# misc.net
KiCad netlist of a schematic drawn in Altium Designer
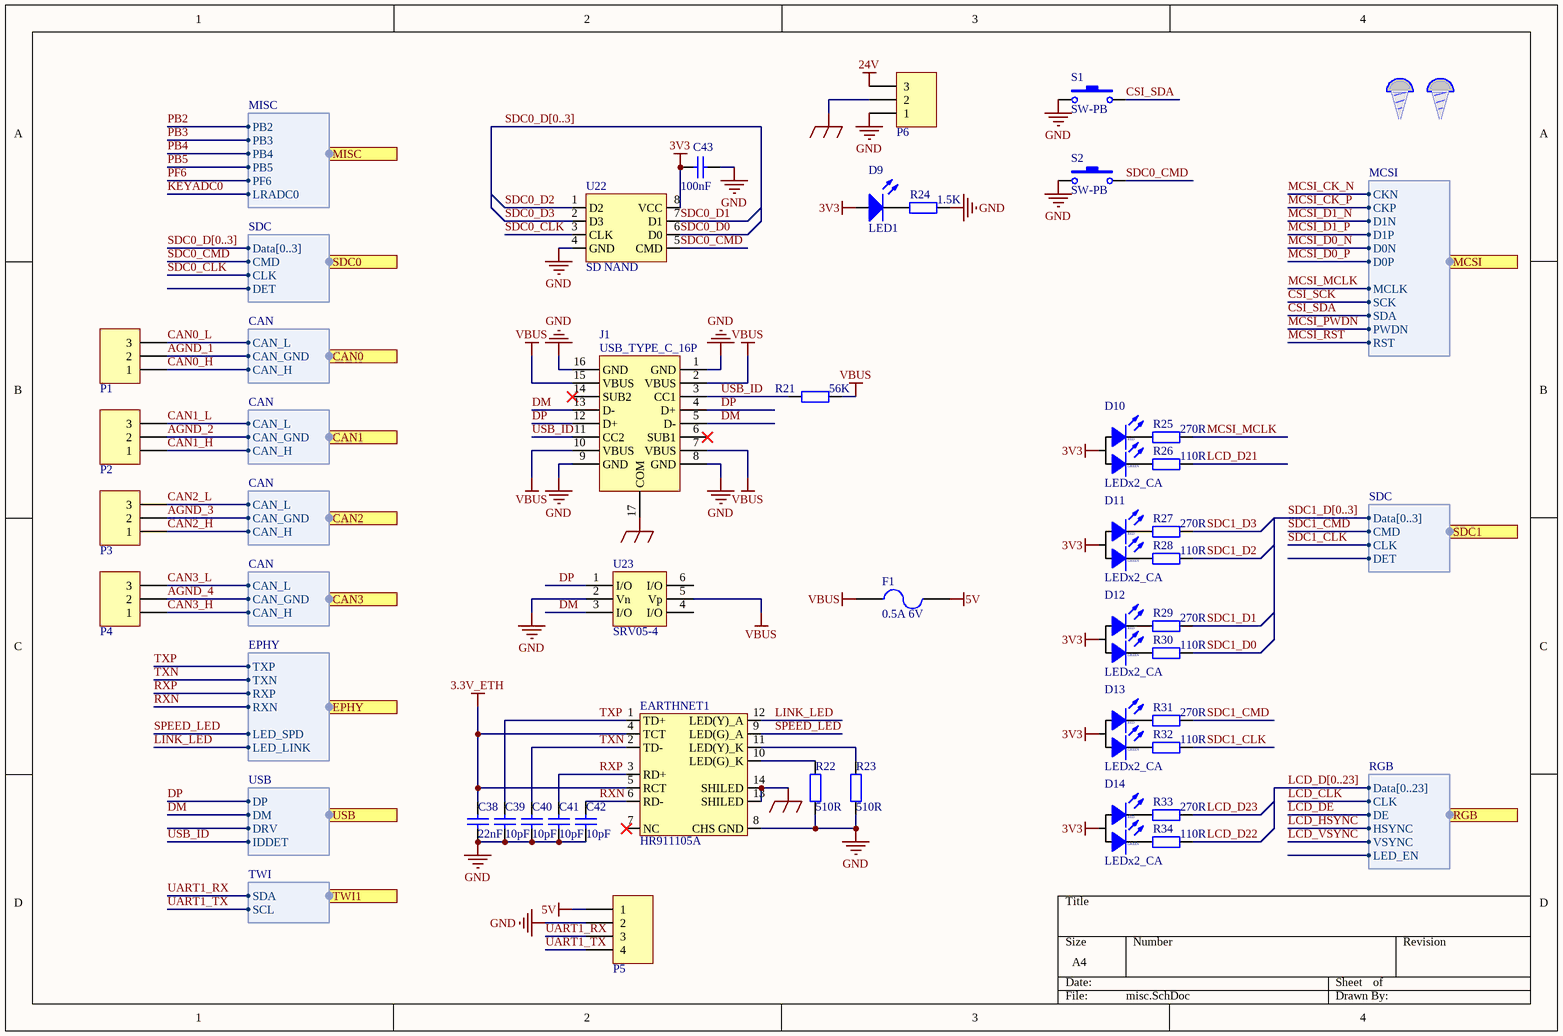
[diagram p0: misc.SchDoc]

(export (version "E")
  (design (tool "Eeschema 10.0.6"))
  (components
    (comp (ref "C38")
      (value "22nF")
      (footprint "CAPC1608L")
      (description "Capacitor")
      (fields (field (name "PUBLISHER") "Altium Limited"))
      (libsource (lib "Peace的集成库") (part "Cap1"))
    )
    (comp (ref "C39")
      (value "10pF")
      (footprint "CAPC1608L")
      (description "Capacitor")
      (fields (field (name "PUBLISHER") "Altium Limited"))
      (libsource (lib "Peace的集成库") (part "Cap1"))
    )
    (comp (ref "C40")
      (value "10pF")
      (footprint "CAPC1608L")
      (description "Capacitor")
      (fields (field (name "PUBLISHER") "Altium Limited"))
      (libsource (lib "Peace的集成库") (part "Cap1"))
    )
    (comp (ref "C41")
      (value "10pF")
      (footprint "CAPC1608L")
      (description "Capacitor")
      (fields (field (name "PUBLISHER") "Altium Limited"))
      (libsource (lib "Peace的集成库") (part "Cap1"))
    )
    (comp (ref "C42")
      (value "10pF")
      (footprint "CAPC1608L")
      (description "Capacitor")
      (fields (field (name "PUBLISHER") "Altium Limited"))
      (libsource (lib "Peace的集成库") (part "Cap1"))
    )
    (comp (ref "C43")
      (value "100nF")
      (footprint "CAPC1608L")
      (description "Capacitor")
      (fields (field (name "PUBLISHER") "Altium Limited"))
      (libsource (lib "Peace的集成库") (part "Cap1"))
    )
    (comp (ref "D9")
      (value "LED1")
      (footprint "LED_3")
      (description "Typical RED GaAs LED")
      (fields (field (name "PUBLISHER") "Altium Limited"))
      (libsource (lib "Peace的集成库") (part "LED1"))
    )
    (comp (ref "D10")
      (value "LEDx2_CA")
      (footprint "LED_3x2")
      (description "共阳红绿双色二极管")
      (fields (field (name "PUBLISHER") "Altium Limited"))
      (libsource (lib "Peace的集成库") (part "LEDx2_CA"))
    )
    (comp (ref "D11")
      (value "LEDx2_CA")
      (footprint "LED_3x2")
      (description "共阳红绿双色二极管")
      (fields (field (name "PUBLISHER") "Altium Limited"))
      (libsource (lib "Peace的集成库") (part "LEDx2_CA"))
    )
    (comp (ref "D12")
      (value "LEDx2_CA")
      (footprint "LED_3x2")
      (description "共阳红绿双色二极管")
      (fields (field (name "PUBLISHER") "Altium Limited"))
      (libsource (lib "Peace的集成库") (part "LEDx2_CA"))
    )
    (comp (ref "D13")
      (value "LEDx2_CA")
      (footprint "LED_3x2")
      (description "共阳红绿双色二极管")
      (fields (field (name "PUBLISHER") "Altium Limited"))
      (libsource (lib "Peace的集成库") (part "LEDx2_CA"))
    )
    (comp (ref "D14")
      (value "LEDx2_CA")
      (footprint "LED_3x2")
      (description "共阳红绿双色二极管")
      (fields (field (name "PUBLISHER") "Altium Limited"))
      (libsource (lib "Peace的集成库") (part "LEDx2_CA"))
    )
    (comp (ref "EARTHNET1")
      (value "HR911105A")
      (footprint "HR911105A")
      (libsource (lib "原理图库") (part "HR911105A"))
    )
    (comp (ref "F1")
      (value "0.5A 6V")
      (footprint "FUSE2012L")
      (description "Fuse")
      (fields (field (name "PUBLISHER") "Altium Limited"))
      (libsource (lib "Peace的集成库") (part "Fuse 2"))
    )
    (comp (ref "J1")
      (value "USB_TYPE_C_16P")
      (footprint "USB_TYPEC_16P")
      (libsource (lib "Peace的集成库") (part "USB_TYPE_C_16P"))
    )
    (comp (ref "M1") (value "M") (footprint "M3") (libsource (lib "Peace的集成库") (part "M")))
    (comp (ref "M2") (value "M") (footprint "M3") (libsource (lib "Peace的集成库") (part "M")))
    (comp (ref "P1")
      (value "Header 3")
      (footprint "KF2EDGR-5.08-3P_S")
      (description "Header, 3-Pin")
      (fields (field (name "PUBLISHER") "Altium Limited"))
      (libsource (lib "Peace的集成库") (part "Header 3"))
    )
    (comp (ref "P2")
      (value "Header 3")
      (footprint "KF2EDGR-5.08-3P_S")
      (description "Header, 3-Pin")
      (fields (field (name "PUBLISHER") "Altium Limited"))
      (libsource (lib "Peace的集成库") (part "Header 3"))
    )
    (comp (ref "P3")
      (value "Header 3")
      (footprint "KF2EDGR-5.08-3P_S")
      (description "Header, 3-Pin")
      (fields (field (name "PUBLISHER") "Altium Limited"))
      (libsource (lib "Peace的集成库") (part "Header 3"))
    )
    (comp (ref "P4")
      (value "Header 3")
      (footprint "KF2EDGR-5.08-3P_S")
      (description "Header, 3-Pin")
      (fields (field (name "PUBLISHER") "Altium Limited"))
      (libsource (lib "Peace的集成库") (part "Header 3"))
    )
    (comp (ref "P5")
      (value "Header 4")
      (footprint "HDR1X4")
      (description "Header, 4-Pin")
      (fields (field (name "PUBLISHER") "Altium Limited"))
      (libsource (lib "Peace的集成库") (part "Header 4"))
    )
    (comp (ref "P6")
      (value "Header 3")
      (footprint "KF2EDGR-5.08-3P_S")
      (description "Header, 3-Pin")
      (fields (field (name "PUBLISHER") "Altium Limited"))
      (libsource (lib "") (part "Header 3_1"))
    )
    (comp (ref "R21")
      (value "56K")
      (footprint "RESC1005L")
      (description "Resistor")
      (fields (field (name "PUBLISHER") "Altium Limited"))
      (libsource (lib "") (part "Res1_1"))
    )
    (comp (ref "R22")
      (value "510R")
      (footprint "RESC1608L")
      (description "Resistor")
      (fields (field (name "PUBLISHER") "Altium Limited"))
      (libsource (lib "Peace的集成库") (part "Res1"))
    )
    (comp (ref "R23")
      (value "510R")
      (footprint "RESC1608L")
      (description "Resistor")
      (fields (field (name "PUBLISHER") "Altium Limited"))
      (libsource (lib "Peace的集成库") (part "Res1"))
    )
    (comp (ref "R24")
      (value "1.5K")
      (footprint "RESC1608L")
      (description "Resistor")
      (fields (field (name "PUBLISHER") "Altium Limited"))
      (libsource (lib "") (part "Res1_1"))
    )
    (comp (ref "R25")
      (value "270R")
      (footprint "RESC1608L")
      (description "Resistor")
      (fields (field (name "PUBLISHER") "Altium Limited"))
      (libsource (lib "") (part "Res1_1"))
    )
    (comp (ref "R26")
      (value "110R")
      (footprint "RESC1608L")
      (description "Resistor")
      (fields (field (name "PUBLISHER") "Altium Limited"))
      (libsource (lib "") (part "Res1_1"))
    )
    (comp (ref "R27")
      (value "270R")
      (footprint "RESC1608L")
      (description "Resistor")
      (fields (field (name "PUBLISHER") "Altium Limited"))
      (libsource (lib "") (part "Res1_1"))
    )
    (comp (ref "R28")
      (value "110R")
      (footprint "RESC1608L")
      (description "Resistor")
      (fields (field (name "PUBLISHER") "Altium Limited"))
      (libsource (lib "") (part "Res1_1"))
    )
    (comp (ref "R29")
      (value "270R")
      (footprint "RESC1608L")
      (description "Resistor")
      (fields (field (name "PUBLISHER") "Altium Limited"))
      (libsource (lib "") (part "Res1_1"))
    )
    (comp (ref "R30")
      (value "110R")
      (footprint "RESC1608L")
      (description "Resistor")
      (fields (field (name "PUBLISHER") "Altium Limited"))
      (libsource (lib "") (part "Res1_1"))
    )
    (comp (ref "R31")
      (value "270R")
      (footprint "RESC1608L")
      (description "Resistor")
      (fields (field (name "PUBLISHER") "Altium Limited"))
      (libsource (lib "") (part "Res1_1"))
    )
    (comp (ref "R32")
      (value "110R")
      (footprint "RESC1608L")
      (description "Resistor")
      (fields (field (name "PUBLISHER") "Altium Limited"))
      (libsource (lib "") (part "Res1_1"))
    )
    (comp (ref "R33")
      (value "270R")
      (footprint "RESC1608L")
      (description "Resistor")
      (fields (field (name "PUBLISHER") "Altium Limited"))
      (libsource (lib "") (part "Res1_1"))
    )
    (comp (ref "R34")
      (value "110R")
      (footprint "RESC1608L")
      (description "Resistor")
      (fields (field (name "PUBLISHER") "Altium Limited"))
      (libsource (lib "") (part "Res1_1"))
    )
    (comp (ref "S1")
      (value "SW-PB")
      (footprint "SW_4.5x3.8")
      (description "Switch")
      (fields (field (name "PUBLISHER") "Altium Limited"))
      (libsource (lib "Peace的集成库") (part "SW-PB"))
    )
    (comp (ref "S2")
      (value "SW-PB")
      (footprint "SW-3x6")
      (description "Switch")
      (fields (field (name "PUBLISHER") "Altium Limited"))
      (libsource (lib "Peace的集成库") (part "SW-PB"))
    )
    (comp (ref "U22")
      (value "SD NAND")
      (footprint "QFN8_L")
      (description "贴片式SD卡")
      (libsource (lib "Peace的集成库") (part "SD NAND"))
    )
    (comp (ref "U23")
      (value "SRV05-4")
      (footprint "SOT23-6_L")
      (libsource (lib "Peace的集成库") (part "NUP4201"))
    )
  )
  (nets
    (net (code "10") (name "/AGND_1") (class "Default")
      (node (ref "P1") (pin "2") (pinfunction "2_2") (pintype "passive"))
    )
    (net (code "11") (name "/AGND_2") (class "Default")
      (node (ref "P2") (pin "2") (pinfunction "2_2") (pintype "passive"))
    )
    (net (code "12") (name "/AGND_3") (class "Default")
      (node (ref "P3") (pin "2") (pinfunction "2_2") (pintype "passive"))
    )
    (net (code "13") (name "/AGND_4") (class "Default")
      (node (ref "P4") (pin "2") (pinfunction "2_2") (pintype "passive"))
    )
    (net (code "14") (name "/CAN0_H") (class "Default")
      (node (ref "P1") (pin "1") (pinfunction "1_1") (pintype "passive"))
    )
    (net (code "15") (name "/CAN0_L") (class "Default")
      (node (ref "P1") (pin "3") (pinfunction "3_3") (pintype "passive"))
    )
    (net (code "16") (name "/CAN1_H") (class "Default")
      (node (ref "P2") (pin "1") (pinfunction "1_1") (pintype "passive"))
    )
    (net (code "17") (name "/CAN1_L") (class "Default")
      (node (ref "P2") (pin "3") (pinfunction "3_3") (pintype "passive"))
    )
    (net (code "18") (name "/CAN2_H") (class "Default")
      (node (ref "P3") (pin "1") (pinfunction "1_1") (pintype "passive"))
    )
    (net (code "19") (name "/CAN2_L") (class "Default")
      (node (ref "P3") (pin "3") (pinfunction "3_3") (pintype "passive"))
    )
    (net (code "20") (name "/CAN3_H") (class "Default")
      (node (ref "P4") (pin "1") (pinfunction "1_1") (pintype "passive"))
    )
    (net (code "21") (name "/CAN3_L") (class "Default")
      (node (ref "P4") (pin "3") (pinfunction "3_3") (pintype "passive"))
    )
    (net (code "23") (name "/CSI_SDA") (class "Default")
      (node (ref "S1") (pin "2") (pinfunction "2_2") (pintype "passive"))
    )
    (net (code "24") (name "/DM") (class "Default")
      (node (ref "J1") (pin "13") (pinfunction "D-_13") (pintype "passive"))
      (node (ref "J1") (pin "5") (pinfunction "D-_5") (pintype "passive"))
      (node (ref "U23") (pin "3") (pinfunction "I/O_3") (pintype "passive"))
    )
    (net (code "25") (name "/DP") (class "Default")
      (node (ref "J1") (pin "12") (pinfunction "D+_12") (pintype "passive"))
      (node (ref "J1") (pin "4") (pinfunction "D+_4") (pintype "passive"))
      (node (ref "U23") (pin "1") (pinfunction "I/O_1") (pintype "passive"))
    )
    (net (code "28") (name "/LCD_D21") (class "Default")
      (node (ref "R26") (pin "2") (pinfunction "2_2") (pintype "passive"))
    )
    (net (code "29") (name "/LCD_D22") (class "Default")
      (node (ref "R34") (pin "2") (pinfunction "2_2") (pintype "passive"))
    )
    (net (code "30") (name "/LCD_D23") (class "Default")
      (node (ref "R33") (pin "2") (pinfunction "2_2") (pintype "passive"))
    )
    (net (code "34") (name "/LINK_LED") (class "Default")
      (node (ref "EARTHNET1") (pin "12") (pinfunction "LED(Y)_A_12") (pintype "passive"))
    )
    (net (code "41") (name "/MCSI_MCLK") (class "Default")
      (node (ref "R25") (pin "2") (pinfunction "2_2") (pintype "passive"))
    )
    (net (code "50") (name "/RXN") (class "Default")
      (node (ref "C42") (pin "2") (pinfunction "2_2") (pintype "passive"))
      (node (ref "EARTHNET1") (pin "6") (pinfunction "RD-_6") (pintype "passive"))
    )
    (net (code "51") (name "/RXP") (class "Default")
      (node (ref "C41") (pin "2") (pinfunction "2_2") (pintype "passive"))
      (node (ref "EARTHNET1") (pin "3") (pinfunction "RD+_3") (pintype "passive"))
    )
    (net (code "52") (name "/SDC0_CLK") (class "Default")
      (node (ref "U22") (pin "3") (pinfunction "CLK_3") (pintype "passive"))
    )
    (net (code "53") (name "/SDC0_CMD") (class "Default")
      (node (ref "S2") (pin "2") (pinfunction "2_2") (pintype "passive"))
      (node (ref "U22") (pin "5") (pinfunction "CMD_5") (pintype "passive"))
    )
    (net (code "54") (name "/SDC0_D0") (class "Default")
      (node (ref "U22") (pin "6") (pinfunction "D0_6") (pintype "passive"))
    )
    (net (code "55") (name "/SDC0_D1") (class "Default")
      (node (ref "U22") (pin "7") (pinfunction "D1_7") (pintype "passive"))
    )
    (net (code "56") (name "/SDC0_D2") (class "Default")
      (node (ref "U22") (pin "1") (pinfunction "D2_1") (pintype "passive"))
    )
    (net (code "57") (name "/SDC0_D3") (class "Default")
      (node (ref "U22") (pin "2") (pinfunction "D3_2") (pintype "passive"))
    )
    (net (code "60") (name "/SDC1_CLK") (class "Default")
      (node (ref "R32") (pin "2") (pinfunction "2_2") (pintype "passive"))
    )
    (net (code "61") (name "/SDC1_CMD") (class "Default")
      (node (ref "R31") (pin "2") (pinfunction "2_2") (pintype "passive"))
    )
    (net (code "62") (name "/SDC1_D0") (class "Default")
      (node (ref "R30") (pin "2") (pinfunction "2_2") (pintype "passive"))
    )
    (net (code "63") (name "/SDC1_D1") (class "Default")
      (node (ref "R29") (pin "2") (pinfunction "2_2") (pintype "passive"))
    )
    (net (code "64") (name "/SDC1_D2") (class "Default")
      (node (ref "R28") (pin "2") (pinfunction "2_2") (pintype "passive"))
    )
    (net (code "65") (name "/SDC1_D3") (class "Default")
      (node (ref "R27") (pin "2") (pinfunction "2_2") (pintype "passive"))
    )
    (net (code "67") (name "/SPEED_LED") (class "Default")
      (node (ref "EARTHNET1") (pin "9") (pinfunction "LED(G)_A_9") (pintype "passive"))
    )
    (net (code "68") (name "/TXN") (class "Default")
      (node (ref "C40") (pin "2") (pinfunction "2_2") (pintype "passive"))
      (node (ref "EARTHNET1") (pin "2") (pinfunction "TD-_2") (pintype "passive"))
    )
    (net (code "69") (name "/TXP") (class "Default")
      (node (ref "C39") (pin "2") (pinfunction "2_2") (pintype "passive"))
      (node (ref "EARTHNET1") (pin "1") (pinfunction "TD+_1") (pintype "passive"))
    )
    (net (code "70") (name "/UART1_RX") (class "Default")
      (node (ref "P5") (pin "3") (pinfunction "3_3") (pintype "passive"))
    )
    (net (code "71") (name "/UART1_TX") (class "Default")
      (node (ref "P5") (pin "4") (pinfunction "4_4") (pintype "passive"))
    )
    (net (code "72") (name "/USB_ID") (class "Default")
      (node (ref "J1") (pin "11") (pinfunction "CC2_11") (pintype "passive"))
      (node (ref "J1") (pin "3") (pinfunction "CC1_3") (pintype "passive"))
      (node (ref "R21") (pin "1") (pinfunction "1_1") (pintype "passive"))
    )
    (net (code "82") (name "3.3V_ETH") (class "Default")
      (node (ref "C38") (pin "2") (pinfunction "2_2") (pintype "passive"))
      (node (ref "EARTHNET1") (pin "4") (pinfunction "TCT_4") (pintype "passive"))
      (node (ref "EARTHNET1") (pin "5") (pinfunction "RCT_5") (pintype "passive"))
    )
    (net (code "83") (name "3V3") (class "Default")
      (node (ref "C43") (pin "1") (pinfunction "1_1") (pintype "passive"))
      (node (ref "D10") (pin "2") (pinfunction "A_2") (pintype "passive"))
      (node (ref "D11") (pin "2") (pinfunction "A_2") (pintype "passive"))
      (node (ref "D12") (pin "2") (pinfunction "A_2") (pintype "passive"))
      (node (ref "D13") (pin "2") (pinfunction "A_2") (pintype "passive"))
      (node (ref "D14") (pin "2") (pinfunction "A_2") (pintype "passive"))
      (node (ref "D9") (pin "1") (pinfunction "A_1") (pintype "passive"))
      (node (ref "U22") (pin "8") (pinfunction "VCC_8") (pintype "passive"))
    )
    (net (code "84") (name "5V") (class "Default")
      (node (ref "F1") (pin "2") (pinfunction "2_2") (pintype "passive"))
      (node (ref "P5") (pin "1") (pinfunction "1_1") (pintype "passive"))
    )
    (net (code "85") (name "24V") (class "Default")
      (node (ref "P6") (pin "3") (pinfunction "3_3") (pintype "passive"))
    )
    (net (code "86") (name "EARTH") (class "Default")
      (node (ref "EARTHNET1") (pin "13") (pinfunction "SHILED_13") (pintype "passive"))
      (node (ref "EARTHNET1") (pin "14") (pinfunction "SHILED_14") (pintype "passive"))
      (node (ref "J1") (pin "17") (pinfunction "COM_17") (pintype "passive"))
      (node (ref "P6") (pin "2") (pinfunction "2_2") (pintype "passive"))
    )
    (net (code "87") (name "GND") (class "Default")
      (node (ref "C38") (pin "1") (pinfunction "1_1") (pintype "passive"))
      (node (ref "C39") (pin "1") (pinfunction "1_1") (pintype "passive"))
      (node (ref "C40") (pin "1") (pinfunction "1_1") (pintype "passive"))
      (node (ref "C41") (pin "1") (pinfunction "1_1") (pintype "passive"))
      (node (ref "C42") (pin "1") (pinfunction "1_1") (pintype "passive"))
      (node (ref "C43") (pin "2") (pinfunction "2_2") (pintype "passive"))
      (node (ref "EARTHNET1") (pin "8") (pinfunction "CHS_GND_8") (pintype "passive"))
      (node (ref "J1") (pin "1") (pinfunction "GND_1") (pintype "passive"))
      (node (ref "J1") (pin "16") (pinfunction "GND_16") (pintype "passive"))
      (node (ref "J1") (pin "8") (pinfunction "GND_8") (pintype "passive"))
      (node (ref "J1") (pin "9") (pinfunction "GND_9") (pintype "passive"))
      (node (ref "P5") (pin "2") (pinfunction "2_2") (pintype "passive"))
      (node (ref "P6") (pin "1") (pinfunction "1_1") (pintype "passive"))
      (node (ref "R22") (pin "1") (pinfunction "1_1") (pintype "passive"))
      (node (ref "R23") (pin "1") (pinfunction "1_1") (pintype "passive"))
      (node (ref "R24") (pin "2") (pinfunction "2_2") (pintype "passive"))
      (node (ref "S1") (pin "1") (pinfunction "1_1") (pintype "passive"))
      (node (ref "S2") (pin "1") (pinfunction "1_1") (pintype "passive"))
      (node (ref "U22") (pin "4") (pinfunction "GND_4") (pintype "passive"))
      (node (ref "U23") (pin "2") (pinfunction "Vn_2") (pintype "passive"))
    )
    (net (code "88") (name "Net-(D9-K)") (class "Default")
      (node (ref "D9") (pin "2") (pinfunction "K_2") (pintype "passive"))
      (node (ref "R24") (pin "1") (pinfunction "1_1") (pintype "passive"))
    )
    (net (code "89") (name "Net-(D10-K-Pad1)") (class "Default")
      (node (ref "D10") (pin "1") (pinfunction "K_1") (pintype "passive"))
      (node (ref "R26") (pin "1") (pinfunction "1_1") (pintype "passive"))
    )
    (net (code "90") (name "Net-(D10-K-Pad3)") (class "Default")
      (node (ref "D10") (pin "3") (pinfunction "K_3") (pintype "passive"))
      (node (ref "R25") (pin "1") (pinfunction "1_1") (pintype "passive"))
    )
    (net (code "91") (name "Net-(D11-K-Pad1)") (class "Default")
      (node (ref "D11") (pin "1") (pinfunction "K_1") (pintype "passive"))
      (node (ref "R28") (pin "1") (pinfunction "1_1") (pintype "passive"))
    )
    (net (code "92") (name "Net-(D11-K-Pad3)") (class "Default")
      (node (ref "D11") (pin "3") (pinfunction "K_3") (pintype "passive"))
      (node (ref "R27") (pin "1") (pinfunction "1_1") (pintype "passive"))
    )
    (net (code "93") (name "Net-(D12-K-Pad1)") (class "Default")
      (node (ref "D12") (pin "1") (pinfunction "K_1") (pintype "passive"))
      (node (ref "R30") (pin "1") (pinfunction "1_1") (pintype "passive"))
    )
    (net (code "94") (name "Net-(D12-K-Pad3)") (class "Default")
      (node (ref "D12") (pin "3") (pinfunction "K_3") (pintype "passive"))
      (node (ref "R29") (pin "1") (pinfunction "1_1") (pintype "passive"))
    )
    (net (code "95") (name "Net-(D13-K-Pad1)") (class "Default")
      (node (ref "D13") (pin "1") (pinfunction "K_1") (pintype "passive"))
      (node (ref "R32") (pin "1") (pinfunction "1_1") (pintype "passive"))
    )
    (net (code "96") (name "Net-(D13-K-Pad3)") (class "Default")
      (node (ref "D13") (pin "3") (pinfunction "K_3") (pintype "passive"))
      (node (ref "R31") (pin "1") (pinfunction "1_1") (pintype "passive"))
    )
    (net (code "97") (name "Net-(D14-K-Pad1)") (class "Default")
      (node (ref "D14") (pin "1") (pinfunction "K_1") (pintype "passive"))
      (node (ref "R34") (pin "1") (pinfunction "1_1") (pintype "passive"))
    )
    (net (code "98") (name "Net-(D14-K-Pad3)") (class "Default")
      (node (ref "D14") (pin "3") (pinfunction "K_3") (pintype "passive"))
      (node (ref "R33") (pin "1") (pinfunction "1_1") (pintype "passive"))
    )
    (net (code "99") (name "Net-(EARTHNET1-LED(G)_K)") (class "Default")
      (node (ref "EARTHNET1") (pin "10") (pinfunction "LED(G)_K_10") (pintype "passive"))
      (node (ref "R22") (pin "2") (pinfunction "2_2") (pintype "passive"))
    )
    (net (code "100") (name "Net-(EARTHNET1-LED(Y)_K)") (class "Default")
      (node (ref "EARTHNET1") (pin "11") (pinfunction "LED(Y)_K_11") (pintype "passive"))
      (node (ref "R23") (pin "2") (pinfunction "2_2") (pintype "passive"))
    )
    (net (code "101") (name "VBUS") (class "Default")
      (node (ref "F1") (pin "1") (pinfunction "1_1") (pintype "passive"))
      (node (ref "J1") (pin "10") (pinfunction "VBUS_10") (pintype "passive"))
      (node (ref "J1") (pin "15") (pinfunction "VBUS_15") (pintype "passive"))
      (node (ref "J1") (pin "2") (pinfunction "VBUS_2") (pintype "passive"))
      (node (ref "J1") (pin "7") (pinfunction "VBUS_7") (pintype "passive"))
      (node (ref "R21") (pin "2") (pinfunction "2_2") (pintype "passive"))
      (node (ref "U23") (pin "5") (pinfunction "Vp_5") (pintype "passive"))
    )
    (net (code "102") (name "unconnected-(EARTHNET1-NC-Pad7)") (class "Default")
      (node (ref "EARTHNET1") (pin "7") (pinfunction "NC_7") (pintype "passive+no_connect"))
    )
    (net (code "103") (name "unconnected-(J1-SUB1-Pad6)") (class "Default")
      (node (ref "J1") (pin "6") (pinfunction "SUB1_6") (pintype "passive+no_connect"))
    )
    (net (code "104") (name "unconnected-(J1-SUB2-Pad14)") (class "Default")
      (node (ref "J1") (pin "14") (pinfunction "SUB2_14") (pintype "passive+no_connect"))
    )
    (net (code "105") (name "unconnected-(U23-I{slash}O-Pad4)") (class "Default")
      (node (ref "U23") (pin "4") (pinfunction "I/O_4") (pintype "passive"))
    )
    (net (code "106") (name "unconnected-(U23-I{slash}O-Pad6)") (class "Default")
      (node (ref "U23") (pin "6") (pinfunction "I/O_6") (pintype "passive"))
    )
  )
)
